# FlowSensor.net
KiCad netlist of a schematic drawn in EAGLE
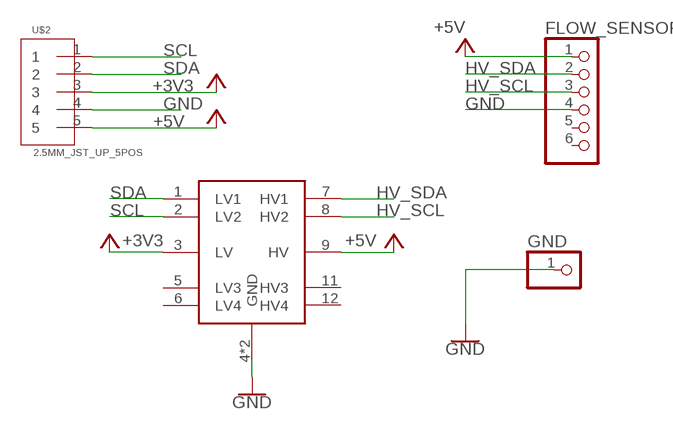
[diagram p0: schematic, sheet 1]

(export (version "E")
  (design (tool "Eeschema 10.0.6"))
  (components
    (comp (ref "FLOW_SENSOR")
      (value "PINHD-1X6")
      (footprint "eagle-import:1X06")
      (libsource (lib "eagle-import") (part "PINHD-1X6"))
    )
    (comp (ref "GND")
      (value "PINHD-1X1")
      (footprint "eagle-import:1X01")
      (libsource (lib "eagle-import") (part "PINHD-1X1"))
    )
    (comp (ref "U$1")
      (value "LOGIC_LEVEL_CONVERTER")
      (footprint "eagle-import:LOGIC_LEVEL_CONVERTER")
      (libsource (lib "eagle-import") (part "LOGIC_LEVEL_CONVERTER"))
    )
    (comp (ref "U$2")
      (value "2.5MM_JST_UP_5POS")
      (footprint "eagle-import:JST_5POS_2.5MM_UP")
      (libsource (lib "eagle-import") (part "2.5MM_JST_UP_5POS"))
    )
  )
  (nets
    (net (code "1") (name "+3V3") (class "Default")
      (node (ref "U$1") (pin "3") (pinfunction "LV_3") (pintype "bidirectional"))
      (node (ref "U$2") (pin "3") (pinfunction "3_3") (pintype "bidirectional"))
    )
    (net (code "2") (name "+5V") (class "Default")
      (node (ref "FLOW_SENSOR") (pin "1") (pinfunction "1_1") (pintype "passive"))
      (node (ref "U$1") (pin "9") (pinfunction "HV_9") (pintype "bidirectional"))
      (node (ref "U$2") (pin "5") (pinfunction "5_5") (pintype "bidirectional"))
    )
    (net (code "3") (name "/HV_SCL") (class "Default")
      (node (ref "FLOW_SENSOR") (pin "3") (pinfunction "3_3") (pintype "passive"))
      (node (ref "U$1") (pin "8") (pinfunction "HV2_8") (pintype "bidirectional"))
    )
    (net (code "4") (name "/HV_SDA") (class "Default")
      (node (ref "FLOW_SENSOR") (pin "2") (pinfunction "2_2") (pintype "passive"))
      (node (ref "U$1") (pin "7") (pinfunction "HV1_7") (pintype "bidirectional"))
    )
    (net (code "5") (name "/SCL") (class "Default")
      (node (ref "U$1") (pin "2") (pinfunction "LV2_2") (pintype "bidirectional"))
      (node (ref "U$2") (pin "1") (pinfunction "1_1") (pintype "bidirectional"))
    )
    (net (code "6") (name "/SDA") (class "Default")
      (node (ref "U$1") (pin "1") (pinfunction "LV1_1") (pintype "bidirectional"))
      (node (ref "U$2") (pin "2") (pinfunction "2_2") (pintype "bidirectional"))
    )
    (net (code "7") (name "GND") (class "Default")
      (node (ref "FLOW_SENSOR") (pin "4") (pinfunction "4_4") (pintype "passive"))
      (node (ref "GND") (pin "1") (pinfunction "1_1") (pintype "passive"))
      (node (ref "U$1") (pin "10") (pinfunction "GND_10") (pintype "bidirectional"))
      (node (ref "U$1") (pin "4") (pinfunction "GND_4") (pintype "bidirectional"))
      (node (ref "U$2") (pin "4") (pinfunction "4_4") (pintype "bidirectional"))
    )
    (net (code "8") (name "unconnected-(FLOW_SENSOR-Pad5)") (class "Default")
      (node (ref "FLOW_SENSOR") (pin "5") (pinfunction "5_5") (pintype "passive"))
    )
    (net (code "9") (name "unconnected-(FLOW_SENSOR-Pad6)") (class "Default")
      (node (ref "FLOW_SENSOR") (pin "6") (pinfunction "6_6") (pintype "passive"))
    )
    (net (code "10") (name "unconnected-(U$1-HV3-Pad11)") (class "Default")
      (node (ref "U$1") (pin "11") (pinfunction "HV3_11") (pintype "bidirectional"))
    )
    (net (code "11") (name "unconnected-(U$1-HV4-Pad12)") (class "Default")
      (node (ref "U$1") (pin "12") (pinfunction "HV4_12") (pintype "bidirectional"))
    )
    (net (code "12") (name "unconnected-(U$1-LV3-Pad5)") (class "Default")
      (node (ref "U$1") (pin "5") (pinfunction "LV3_5") (pintype "bidirectional"))
    )
    (net (code "13") (name "unconnected-(U$1-LV4-Pad6)") (class "Default")
      (node (ref "U$1") (pin "6") (pinfunction "LV4_6") (pintype "bidirectional"))
    )
  )
)
